# Spin_board2.net
KiCad netlist of a schematic drawn in EAGLE
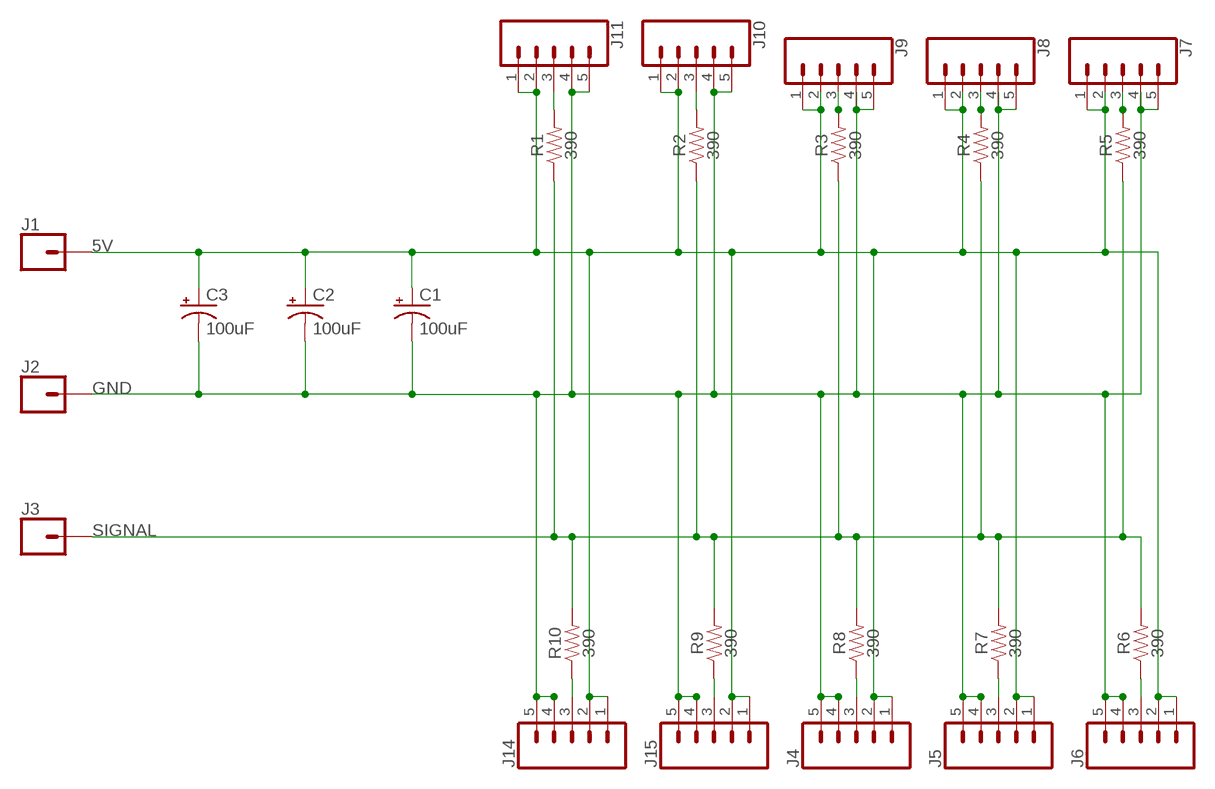
[diagram p0: schematic, sheet 1]

(export (version "E")
  (design (tool "Eeschema 10.0.6"))
  (components
    (comp (ref "C1")
      (value "100uF")
      (footprint "eagle-import:CPOL-RADIAL-2.5MM-6.5MM")
      (libsource (lib "eagle-import") (part "100UF-POLAR-RADIAL-2.5MM-25V-20%"))
    )
    (comp (ref "C2")
      (value "100uF")
      (footprint "eagle-import:CPOL-RADIAL-2.5MM-6.5MM")
      (libsource (lib "eagle-import") (part "100UF-POLAR-RADIAL-2.5MM-25V-20%"))
    )
    (comp (ref "C3")
      (value "100uF")
      (footprint "eagle-import:CPOL-RADIAL-2.5MM-6.5MM")
      (libsource (lib "eagle-import") (part "100UF-POLAR-RADIAL-2.5MM-25V-20%"))
    )
    (comp (ref "J1")
      (value "CONN_01")
      (footprint "eagle-import:1X01")
      (libsource (lib "eagle-import") (part "CONN_01"))
    )
    (comp (ref "J2")
      (value "CONN_01")
      (footprint "eagle-import:1X01")
      (libsource (lib "eagle-import") (part "CONN_01"))
    )
    (comp (ref "J3")
      (value "CONN_01")
      (footprint "eagle-import:1X01")
      (libsource (lib "eagle-import") (part "CONN_01"))
    )
    (comp (ref "J4")
      (value "CONN_05SMD")
      (footprint "eagle-import:1X05_1MM")
      (libsource (lib "eagle-import") (part "CONN_05SMD"))
    )
    (comp (ref "J5")
      (value "CONN_05SMD")
      (footprint "eagle-import:1X05_1MM")
      (libsource (lib "eagle-import") (part "CONN_05SMD"))
    )
    (comp (ref "J6")
      (value "CONN_05SMD")
      (footprint "eagle-import:1X05_1MM")
      (libsource (lib "eagle-import") (part "CONN_05SMD"))
    )
    (comp (ref "J7")
      (value "CONN_05SMD")
      (footprint "eagle-import:1X05_1MM")
      (libsource (lib "eagle-import") (part "CONN_05SMD"))
    )
    (comp (ref "J8")
      (value "CONN_05SMD")
      (footprint "eagle-import:1X05_1MM")
      (libsource (lib "eagle-import") (part "CONN_05SMD"))
    )
    (comp (ref "J9")
      (value "CONN_05SMD")
      (footprint "eagle-import:1X05_1MM")
      (libsource (lib "eagle-import") (part "CONN_05SMD"))
    )
    (comp (ref "J10")
      (value "CONN_05SMD")
      (footprint "eagle-import:1X05_1MM")
      (libsource (lib "eagle-import") (part "CONN_05SMD"))
    )
    (comp (ref "J11")
      (value "CONN_05SMD")
      (footprint "eagle-import:1X05_1MM")
      (libsource (lib "eagle-import") (part "CONN_05SMD"))
    )
    (comp (ref "J14")
      (value "CONN_05SMD")
      (footprint "eagle-import:1X05_1MM")
      (libsource (lib "eagle-import") (part "CONN_05SMD"))
    )
    (comp (ref "J15")
      (value "CONN_05SMD")
      (footprint "eagle-import:1X05_1MM")
      (libsource (lib "eagle-import") (part "CONN_05SMD"))
    )
    (comp (ref "R1")
      (value "390")
      (footprint "eagle-import:0603")
      (libsource (lib "eagle-import") (part "390OHM-0603-1/10W-1%"))
    )
    (comp (ref "R2")
      (value "390")
      (footprint "eagle-import:0603")
      (libsource (lib "eagle-import") (part "390OHM-0603-1/10W-1%"))
    )
    (comp (ref "R3")
      (value "390")
      (footprint "eagle-import:0603")
      (libsource (lib "eagle-import") (part "390OHM-0603-1/10W-1%"))
    )
    (comp (ref "R4")
      (value "390")
      (footprint "eagle-import:0603")
      (libsource (lib "eagle-import") (part "390OHM-0603-1/10W-1%"))
    )
    (comp (ref "R5")
      (value "390")
      (footprint "eagle-import:0603")
      (libsource (lib "eagle-import") (part "390OHM-0603-1/10W-1%"))
    )
    (comp (ref "R6")
      (value "390")
      (footprint "eagle-import:0603")
      (libsource (lib "eagle-import") (part "390OHM-0603-1/10W-1%"))
    )
    (comp (ref "R7")
      (value "390")
      (footprint "eagle-import:0603")
      (libsource (lib "eagle-import") (part "390OHM-0603-1/10W-1%"))
    )
    (comp (ref "R8")
      (value "390")
      (footprint "eagle-import:0603")
      (libsource (lib "eagle-import") (part "390OHM-0603-1/10W-1%"))
    )
    (comp (ref "R9")
      (value "390")
      (footprint "eagle-import:0603")
      (libsource (lib "eagle-import") (part "390OHM-0603-1/10W-1%"))
    )
    (comp (ref "R10")
      (value "390")
      (footprint "eagle-import:0603")
      (libsource (lib "eagle-import") (part "390OHM-0603-1/10W-1%"))
    )
  )
  (nets
    (net (code "1") (name "/5V") (class "Default")
      (node (ref "C1") (pin "1") (pinfunction "+_1") (pintype "passive"))
      (node (ref "C2") (pin "1") (pinfunction "+_1") (pintype "passive"))
      (node (ref "C3") (pin "1") (pinfunction "+_1") (pintype "passive"))
      (node (ref "J1") (pin "1") (pinfunction "1_1") (pintype "passive"))
      (node (ref "J10") (pin "1") (pinfunction "1_1") (pintype "passive"))
      (node (ref "J10") (pin "2") (pinfunction "2_2") (pintype "passive"))
      (node (ref "J11") (pin "1") (pinfunction "1_1") (pintype "passive"))
      (node (ref "J11") (pin "2") (pinfunction "2_2") (pintype "passive"))
      (node (ref "J14") (pin "1") (pinfunction "1_1") (pintype "passive"))
      (node (ref "J14") (pin "2") (pinfunction "2_2") (pintype "passive"))
      (node (ref "J15") (pin "1") (pinfunction "1_1") (pintype "passive"))
      (node (ref "J15") (pin "2") (pinfunction "2_2") (pintype "passive"))
      (node (ref "J4") (pin "1") (pinfunction "1_1") (pintype "passive"))
      (node (ref "J4") (pin "2") (pinfunction "2_2") (pintype "passive"))
      (node (ref "J5") (pin "1") (pinfunction "1_1") (pintype "passive"))
      (node (ref "J5") (pin "2") (pinfunction "2_2") (pintype "passive"))
      (node (ref "J6") (pin "1") (pinfunction "1_1") (pintype "passive"))
      (node (ref "J6") (pin "2") (pinfunction "2_2") (pintype "passive"))
      (node (ref "J7") (pin "1") (pinfunction "1_1") (pintype "passive"))
      (node (ref "J7") (pin "2") (pinfunction "2_2") (pintype "passive"))
      (node (ref "J8") (pin "1") (pinfunction "1_1") (pintype "passive"))
      (node (ref "J8") (pin "2") (pinfunction "2_2") (pintype "passive"))
      (node (ref "J9") (pin "1") (pinfunction "1_1") (pintype "passive"))
      (node (ref "J9") (pin "2") (pinfunction "2_2") (pintype "passive"))
    )
    (net (code "2") (name "/GND") (class "Default")
      (node (ref "C1") (pin "2") (pinfunction "-_2") (pintype "passive"))
      (node (ref "C2") (pin "2") (pinfunction "-_2") (pintype "passive"))
      (node (ref "C3") (pin "2") (pinfunction "-_2") (pintype "passive"))
      (node (ref "J10") (pin "4") (pinfunction "4_4") (pintype "passive"))
      (node (ref "J10") (pin "5") (pinfunction "5_5") (pintype "passive"))
      (node (ref "J11") (pin "4") (pinfunction "4_4") (pintype "passive"))
      (node (ref "J11") (pin "5") (pinfunction "5_5") (pintype "passive"))
      (node (ref "J14") (pin "4") (pinfunction "4_4") (pintype "passive"))
      (node (ref "J14") (pin "5") (pinfunction "5_5") (pintype "passive"))
      (node (ref "J15") (pin "4") (pinfunction "4_4") (pintype "passive"))
      (node (ref "J15") (pin "5") (pinfunction "5_5") (pintype "passive"))
      (node (ref "J2") (pin "1") (pinfunction "1_1") (pintype "passive"))
      (node (ref "J4") (pin "4") (pinfunction "4_4") (pintype "passive"))
      (node (ref "J4") (pin "5") (pinfunction "5_5") (pintype "passive"))
      (node (ref "J5") (pin "4") (pinfunction "4_4") (pintype "passive"))
      (node (ref "J5") (pin "5") (pinfunction "5_5") (pintype "passive"))
      (node (ref "J6") (pin "4") (pinfunction "4_4") (pintype "passive"))
      (node (ref "J6") (pin "5") (pinfunction "5_5") (pintype "passive"))
      (node (ref "J7") (pin "4") (pinfunction "4_4") (pintype "passive"))
      (node (ref "J7") (pin "5") (pinfunction "5_5") (pintype "passive"))
      (node (ref "J8") (pin "4") (pinfunction "4_4") (pintype "passive"))
      (node (ref "J8") (pin "5") (pinfunction "5_5") (pintype "passive"))
      (node (ref "J9") (pin "4") (pinfunction "4_4") (pintype "passive"))
      (node (ref "J9") (pin "5") (pinfunction "5_5") (pintype "passive"))
    )
    (net (code "3") (name "/SIGNAL") (class "Default")
      (node (ref "J3") (pin "1") (pinfunction "1_1") (pintype "passive"))
      (node (ref "R1") (pin "1") (pinfunction "1_1") (pintype "passive"))
      (node (ref "R10") (pin "2") (pinfunction "2_2") (pintype "passive"))
      (node (ref "R2") (pin "1") (pinfunction "1_1") (pintype "passive"))
      (node (ref "R3") (pin "1") (pinfunction "1_1") (pintype "passive"))
      (node (ref "R4") (pin "1") (pinfunction "1_1") (pintype "passive"))
      (node (ref "R5") (pin "1") (pinfunction "1_1") (pintype "passive"))
      (node (ref "R6") (pin "2") (pinfunction "2_2") (pintype "passive"))
      (node (ref "R7") (pin "2") (pinfunction "2_2") (pintype "passive"))
      (node (ref "R8") (pin "2") (pinfunction "2_2") (pintype "passive"))
      (node (ref "R9") (pin "2") (pinfunction "2_2") (pintype "passive"))
    )
    (net (code "4") (name "Net-(J4-Pad3)") (class "Default")
      (node (ref "J4") (pin "3") (pinfunction "3_3") (pintype "passive"))
      (node (ref "R8") (pin "1") (pinfunction "1_1") (pintype "passive"))
    )
    (net (code "5") (name "Net-(J5-Pad3)") (class "Default")
      (node (ref "J5") (pin "3") (pinfunction "3_3") (pintype "passive"))
      (node (ref "R7") (pin "1") (pinfunction "1_1") (pintype "passive"))
    )
    (net (code "6") (name "Net-(J6-Pad3)") (class "Default")
      (node (ref "J6") (pin "3") (pinfunction "3_3") (pintype "passive"))
      (node (ref "R6") (pin "1") (pinfunction "1_1") (pintype "passive"))
    )
    (net (code "7") (name "Net-(J7-Pad3)") (class "Default")
      (node (ref "J7") (pin "3") (pinfunction "3_3") (pintype "passive"))
      (node (ref "R5") (pin "2") (pinfunction "2_2") (pintype "passive"))
    )
    (net (code "8") (name "Net-(J8-Pad3)") (class "Default")
      (node (ref "J8") (pin "3") (pinfunction "3_3") (pintype "passive"))
      (node (ref "R4") (pin "2") (pinfunction "2_2") (pintype "passive"))
    )
    (net (code "9") (name "Net-(J9-Pad3)") (class "Default")
      (node (ref "J9") (pin "3") (pinfunction "3_3") (pintype "passive"))
      (node (ref "R3") (pin "2") (pinfunction "2_2") (pintype "passive"))
    )
    (net (code "10") (name "Net-(J10-Pad3)") (class "Default")
      (node (ref "J10") (pin "3") (pinfunction "3_3") (pintype "passive"))
      (node (ref "R2") (pin "2") (pinfunction "2_2") (pintype "passive"))
    )
    (net (code "11") (name "Net-(J11-Pad3)") (class "Default")
      (node (ref "J11") (pin "3") (pinfunction "3_3") (pintype "passive"))
      (node (ref "R1") (pin "2") (pinfunction "2_2") (pintype "passive"))
    )
    (net (code "12") (name "Net-(J14-Pad3)") (class "Default")
      (node (ref "J14") (pin "3") (pinfunction "3_3") (pintype "passive"))
      (node (ref "R10") (pin "1") (pinfunction "1_1") (pintype "passive"))
    )
    (net (code "13") (name "Net-(J15-Pad3)") (class "Default")
      (node (ref "J15") (pin "3") (pinfunction "3_3") (pintype "passive"))
      (node (ref "R9") (pin "1") (pinfunction "1_1") (pintype "passive"))
    )
  )
)
